# c128power.net
KiCad netlist of a schematic drawn in EAGLE
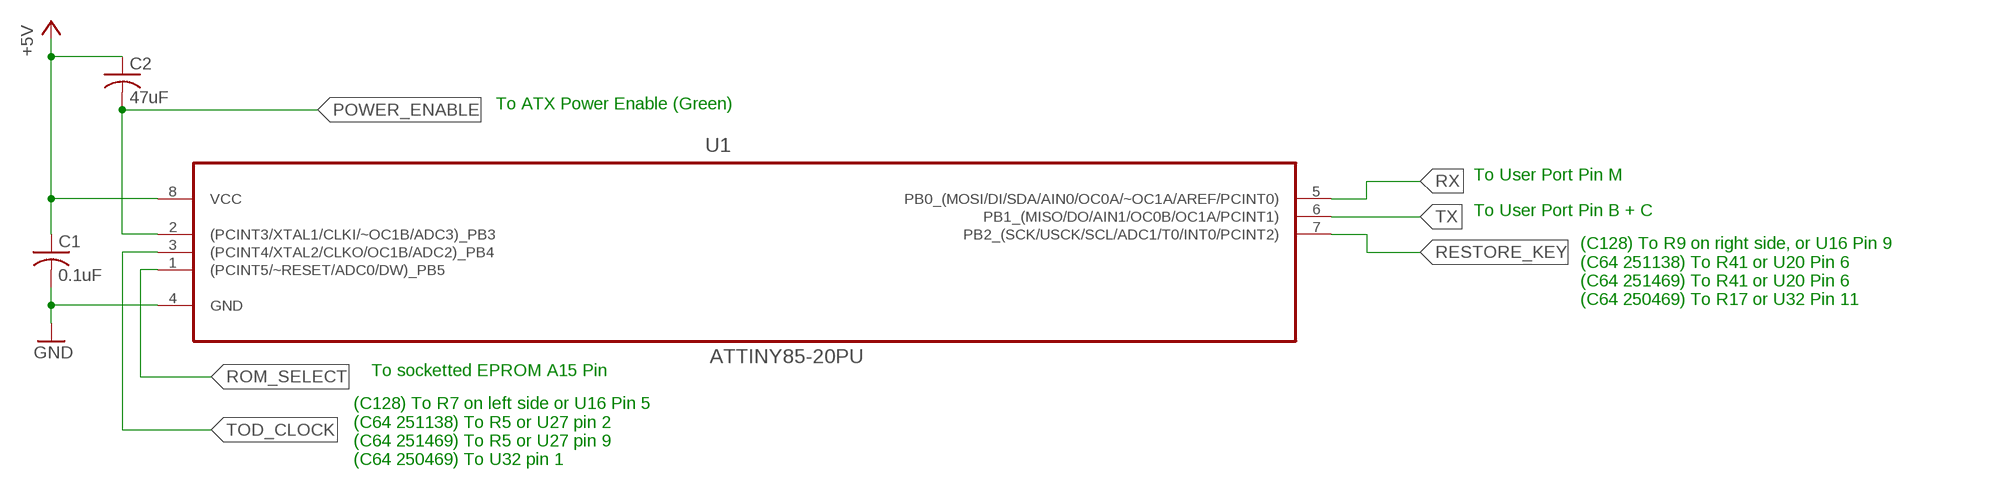
[diagram p0: schematic, sheet 1]

(export (version "E")
  (design (tool "Eeschema 10.0.6"))
  (components
    (comp (ref "C1")
      (value "0.1uF")
      (footprint "eagle-import:C050-024X044")
      (libsource (lib "eagle-import") (part "C-US050-024X044"))
    )
    (comp (ref "C2")
      (value "47uF")
      (footprint "eagle-import:C050-024X044")
      (libsource (lib "eagle-import") (part "C-US050-024X044"))
    )
    (comp (ref "U1")
      (value "ATTINY85-20PU")
      (footprint "eagle-import:DIP254P762X533-8")
      (libsource (lib "eagle-import") (part "ATTINY85-20PU"))
    )
  )
  (nets
    (net (code "1") (name "+5V") (class "Default")
      (node (ref "C1") (pin "1") (pinfunction "1_1") (pintype "passive"))
      (node (ref "C2") (pin "1") (pinfunction "1_1") (pintype "passive"))
      (node (ref "U1") (pin "8") (pinfunction "VCC_8") (pintype "power_in"))
    )
    (net (code "2") (name "GND") (class "Default")
      (node (ref "C1") (pin "2") (pinfunction "2_2") (pintype "passive"))
      (node (ref "U1") (pin "4") (pinfunction "GND_4") (pintype "passive"))
    )
    (net (code "3") (name "POWER_ENABLE") (class "Default")
      (node (ref "C2") (pin "2") (pinfunction "2_2") (pintype "passive"))
      (node (ref "U1") (pin "2") (pinfunction "(PCINT3/XTAL1/CLKI/~{OC1B/ADC3})_PB3_2") (pintype "bidirectional"))
    )
    (net (code "4") (name "RESTORE_KEY") (class "Default")
      (node (ref "U1") (pin "7") (pinfunction "PB2_(SCK/USCK/SCL/ADC1/T0/INT0/PCINT2)_7") (pintype "bidirectional"))
    )
    (net (code "5") (name "ROM_SELECT") (class "Default")
      (node (ref "U1") (pin "1") (pinfunction "(PCINT5/~{RESET/ADC0/DW})_PB5_1") (pintype "bidirectional"))
    )
    (net (code "6") (name "RX") (class "Default")
      (node (ref "U1") (pin "5") (pinfunction "PB0_(MOSI/DI/SDA/AIN0/OC0A/~{OC1A/AREF/PCINT0})_5") (pintype "bidirectional"))
    )
    (net (code "7") (name "TOD_CLOCK") (class "Default")
      (node (ref "U1") (pin "3") (pinfunction "(PCINT4/XTAL2/CLKO/OC1B/ADC2)_PB4_3") (pintype "bidirectional"))
    )
    (net (code "8") (name "TX") (class "Default")
      (node (ref "U1") (pin "6") (pinfunction "PB1_(MISO/DO/AIN1/OC0B/OC1A/PCINT1)_6") (pintype "bidirectional"))
    )
  )
)
